# top_board_3_6.net
KiCad netlist of a schematic drawn in EAGLE
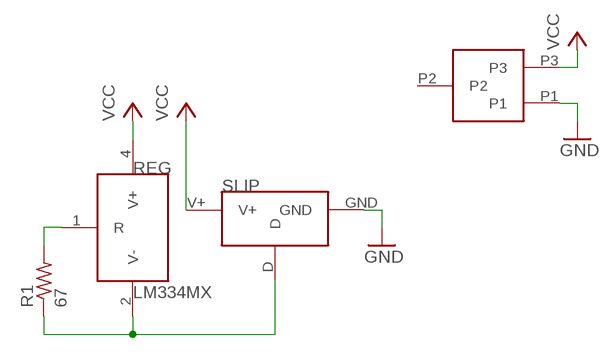
[diagram p0: schematic, sheet 1]

(export (version "E")
  (design (tool "Eeschema 10.0.6"))
  (components
    (comp (ref "R1")
      (value "67")
      (footprint "eagle-import:R0603")
      (libsource (lib "eagle-import") (part "R-US_R0603"))
    )
    (comp (ref "REG")
      (value "LM334MX")
      (footprint "eagle-import:8-SOIC")
      (libsource (lib "eagle-import") (part "LM334MX"))
    )
    (comp (ref "SLIP")
      (value "RING2")
      (footprint "eagle-import:RING2")
      (libsource (lib "eagle-import") (part "RING2"))
    )
    (comp (ref "U$2")
      (value "AVX_CONN")
      (footprint "eagle-import:AVX_CONN")
      (libsource (lib "eagle-import") (part "AVX_CONN"))
    )
  )
  (nets
    (net (code "1") (name "GND") (class "Default")
      (node (ref "SLIP") (pin "GND") (pinfunction "GND_GND") (pintype "bidirectional"))
      (node (ref "U$2") (pin "P1") (pinfunction "P1_P1") (pintype "bidirectional"))
    )
    (net (code "2") (name "Net-(REG-R)") (class "Default")
      (node (ref "R1") (pin "2") (pinfunction "2_2") (pintype "passive"))
      (node (ref "REG") (pin "1") (pinfunction "R_1") (pintype "bidirectional"))
    )
    (net (code "3") (name "Net-(REG-V-)") (class "Default")
      (node (ref "R1") (pin "1") (pinfunction "1_1") (pintype "passive"))
      (node (ref "REG") (pin "2") (pinfunction "V-_2") (pintype "bidirectional"))
      (node (ref "SLIP") (pin "D") (pinfunction "D_D") (pintype "bidirectional"))
    )
    (net (code "4") (name "VCC") (class "Default")
      (node (ref "REG") (pin "4") (pinfunction "V+_4") (pintype "bidirectional"))
      (node (ref "SLIP") (pin "V+") (pinfunction "V+_V+") (pintype "bidirectional"))
      (node (ref "U$2") (pin "P3") (pinfunction "P3_P3") (pintype "bidirectional"))
    )
    (net (code "5") (name "unconnected-(U$2-PadP2)") (class "Default")
      (node (ref "U$2") (pin "P2") (pinfunction "P2_P2") (pintype "bidirectional"))
    )
  )
)
